# MCU.net
KiCad netlist of a schematic drawn in Altium Designer
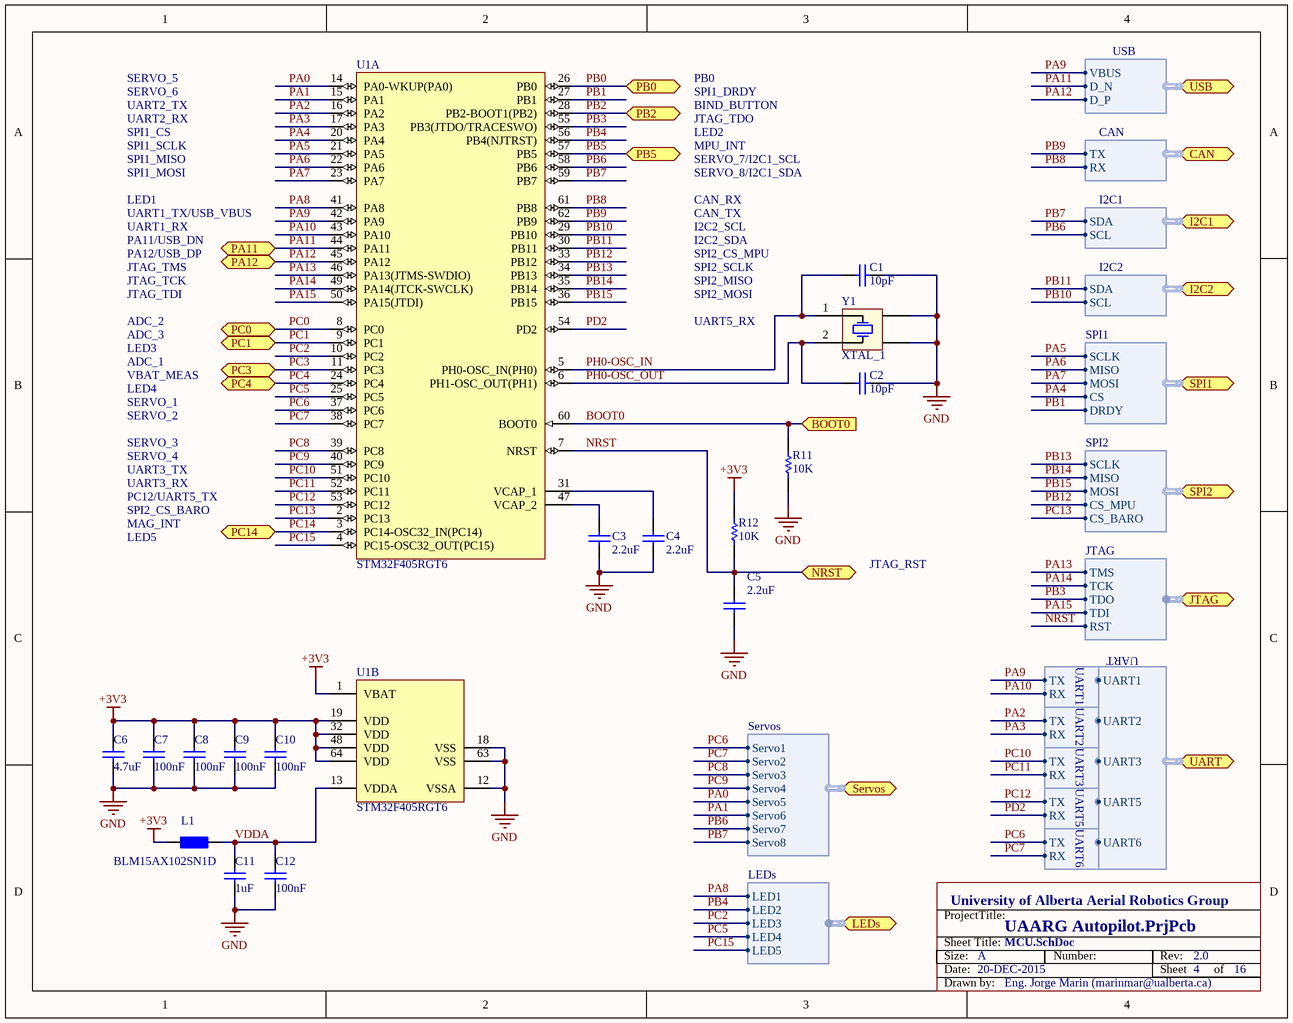
[diagram p0: MCU.SchDoc]

(export (version "E")
  (design (tool "Eeschema 10.0.6"))
  (components
    (comp (ref "C1")
      (value "10pF")
      (footprint "CAP_0402[1005M]")
      (description "Capacitor")
      (fields
        (field (name "MANUFACTURER PART NUMBER") "CC0402JRNPO9BN100")
        (field (name "MANUFACTURER") "Yageo")
      )
      (libsource (lib "UAARG Autopilot") (part "CAP"))
    )
    (comp (ref "C2")
      (value "10pF")
      (footprint "CAP_0402[1005M]")
      (description "Capacitor")
      (fields
        (field (name "MANUFACTURER PART NUMBER") "CC0402JRNPO9BN100")
        (field (name "MANUFACTURER") "Yageo")
      )
      (libsource (lib "UAARG Autopilot") (part "CAP"))
    )
    (comp (ref "C3")
      (value "2.2uF")
      (footprint "CAP_0402[1005M]")
      (description "Capacitor")
      (fields
        (field (name "MANUFACTURER") "Yageo")
        (field (name "MANUFACTURER PART NUMBER") "CC0402MRX5R5BB225")
      )
      (libsource (lib "UAARG Autopilot") (part "CAP"))
    )
    (comp (ref "C4")
      (value "2.2uF")
      (footprint "CAP_0402[1005M]")
      (description "Capacitor")
      (fields
        (field (name "MANUFACTURER") "Yageo")
        (field (name "MANUFACTURER PART NUMBER") "CC0402MRX5R5BB225")
      )
      (libsource (lib "UAARG Autopilot") (part "CAP"))
    )
    (comp (ref "C5")
      (value "2.2uF")
      (footprint "CAP_0402[1005M]")
      (description "Capacitor")
      (fields
        (field (name "MANUFACTURER") "Yageo")
        (field (name "MANUFACTURER PART NUMBER") "CC0402MRX5R5BB225")
      )
      (libsource (lib "UAARG Autopilot") (part "CAP"))
    )
    (comp (ref "C6")
      (value "4.7uF")
      (footprint "CAP_0603[1608M]")
      (description "Capacitor")
      (fields
        (field (name "MANUFACTURER") "Yageo")
        (field (name "MANUFACTURER PART NUMBER") "CC0603KRX5R6BB475")
      )
      (libsource (lib "UAARG Autopilot") (part "CAP"))
    )
    (comp (ref "C7")
      (value "100nF")
      (footprint "CAP_0402[1005M]")
      (description "CAP CER 0.1UF 10V 10% X7R 0402")
      (fields
        (field (name "MANUFACTURER") "Yageo")
        (field (name "MANUFACTURER PART NUMBER") "CC0402KRX7R6BB104")
      )
      (libsource (lib "UAARG Autopilot") (part "CAP"))
    )
    (comp (ref "C8")
      (value "100nF")
      (footprint "CAP_0402[1005M]")
      (description "CAP CER 0.1UF 10V 10% X7R 0402")
      (fields
        (field (name "MANUFACTURER") "Yageo")
        (field (name "MANUFACTURER PART NUMBER") "CC0402KRX7R6BB104")
      )
      (libsource (lib "UAARG Autopilot") (part "CAP"))
    )
    (comp (ref "C9")
      (value "100nF")
      (footprint "CAP_0402[1005M]")
      (description "CAP CER 0.1UF 10V 10% X7R 0402")
      (fields
        (field (name "MANUFACTURER") "Yageo")
        (field (name "MANUFACTURER PART NUMBER") "CC0402KRX7R6BB104")
      )
      (libsource (lib "UAARG Autopilot") (part "CAP"))
    )
    (comp (ref "C10")
      (value "100nF")
      (footprint "CAP_0402[1005M]")
      (description "CAP CER 0.1UF 10V 10% X7R 0402")
      (fields
        (field (name "MANUFACTURER") "Yageo")
        (field (name "MANUFACTURER PART NUMBER") "CC0402KRX7R6BB104")
      )
      (libsource (lib "UAARG Autopilot") (part "CAP"))
    )
    (comp (ref "C11")
      (value "1uF")
      (footprint "CAP_0402[1005M]")
      (description "Capacitor")
      (fields
        (field (name "MANUFACTURER PART NUMBER") "CC0402KRX5R5BB105")
        (field (name "MANUFACTURER") "Yageo")
      )
      (libsource (lib "UAARG Autopilot") (part "CAP"))
    )
    (comp (ref "C12")
      (value "100nF")
      (footprint "CAP_0402[1005M]")
      (description "CAP CER 0.1UF 10V 10% X7R 0402")
      (fields
        (field (name "MANUFACTURER") "Yageo")
        (field (name "MANUFACTURER PART NUMBER") "CC0402KRX7R6BB104")
      )
      (libsource (lib "UAARG Autopilot") (part "CAP"))
    )
    (comp (ref "L1")
      (value "BLM15AX102SN1D")
      (footprint "GEN_0402[1005M]")
      (description "BEAD FERRITE")
      (fields
        (field (name "MANUFACTURER") "Murata Electronics North America")
        (field (name "MANUFACTURER PART NUMBER") "BLM15AX102SN1D")
      )
      (libsource (lib "UAARG Autopilot") (part "Bead Ferrite"))
    )
    (comp (ref "R11")
      (value "10K")
      (footprint "RES_0402[1005M]")
      (description "Resistor")
      (fields
        (field (name "MANUFACTURER") "Yageo")
        (field (name "MANUFACTURER PART NUMBER") "RC0402FR-0710KL")
      )
      (libsource (lib "UAARG Autopilot") (part "RES"))
    )
    (comp (ref "R12")
      (value "10K")
      (footprint "RES_0402[1005M]")
      (description "Resistor")
      (fields
        (field (name "MANUFACTURER") "Yageo")
        (field (name "MANUFACTURER PART NUMBER") "RC0402FR-0710KL")
      )
      (libsource (lib "UAARG Autopilot") (part "RES"))
    )
    (comp (ref "U1")
      (value "STM32F405RGT6")
      (footprint "STM-LQFP64_N")
      (fields (field (name "MANUFACTURER") "STMicroelectronics"))
      (libsource (lib "UAARG Autopilot") (part "STM32F405RGT6"))
    )
    (comp (ref "Y1")
      (value "XTAL_1")
      (footprint "CRYSTAL SMD3 ABM8G 3225")
      (description "Crystal Oscillator with ground points")
      (fields
        (field (name "MANUFACTURER") "Abracon LLC")
        (field (name "MANUFACTURER PART NUMBER") "ABM8G-12.000MHZ-4Y-T3")
      )
      (libsource (lib "UAARG Autopilot") (part "XTAL_1"))
    )
  )
  (nets
    (net (code "11") (name "+3V3") (class "Default")
      (node (ref "C10") (pin "1") (pinfunction "1_1") (pintype "passive"))
      (node (ref "C6") (pin "2") (pinfunction "2_2") (pintype "passive"))
      (node (ref "C7") (pin "1") (pinfunction "1_1") (pintype "passive"))
      (node (ref "C8") (pin "1") (pinfunction "1_1") (pintype "passive"))
      (node (ref "C9") (pin "1") (pinfunction "1_1") (pintype "passive"))
      (node (ref "L1") (pin "1") (pinfunction "1_1") (pintype "passive"))
      (node (ref "R12") (pin "2") (pinfunction "2_2") (pintype "passive"))
      (node (ref "U1") (pin "1") (pinfunction "VBAT_1") (pintype "power_in"))
      (node (ref "U1") (pin "19") (pinfunction "VDD_19") (pintype "power_in"))
      (node (ref "U1") (pin "32") (pinfunction "VDD_32") (pintype "power_in"))
      (node (ref "U1") (pin "48") (pinfunction "VDD_48") (pintype "power_in"))
      (node (ref "U1") (pin "64") (pinfunction "VDD_64") (pintype "power_in"))
    )
    (net (code "12") (name "/BOOT0") (class "Default")
      (node (ref "R11") (pin "2") (pinfunction "2_2") (pintype "passive"))
      (node (ref "U1") (pin "60") (pinfunction "BOOT0_60") (pintype "input"))
    )
    (net (code "13") (name "/NRST") (class "Default")
      (node (ref "C5") (pin "2") (pinfunction "2_2") (pintype "passive"))
      (node (ref "R12") (pin "1") (pinfunction "1_1") (pintype "passive"))
      (node (ref "U1") (pin "7") (pinfunction "NRST_7") (pintype "bidirectional"))
    )
    (net (code "14") (name "/PA0") (class "Default")
      (node (ref "U1") (pin "14") (pinfunction "PA0-WKUP(PA0)_14") (pintype "bidirectional"))
    )
    (net (code "15") (name "/PA1") (class "Default")
      (node (ref "U1") (pin "15") (pinfunction "PA1_15") (pintype "bidirectional"))
    )
    (net (code "16") (name "/PA2") (class "Default")
      (node (ref "U1") (pin "16") (pinfunction "PA2_16") (pintype "bidirectional"))
    )
    (net (code "17") (name "/PA3") (class "Default")
      (node (ref "U1") (pin "17") (pinfunction "PA3_17") (pintype "bidirectional"))
    )
    (net (code "18") (name "/PA4") (class "Default")
      (node (ref "U1") (pin "20") (pinfunction "PA4_20") (pintype "bidirectional"))
    )
    (net (code "19") (name "/PA5") (class "Default")
      (node (ref "U1") (pin "21") (pinfunction "PA5_21") (pintype "bidirectional"))
    )
    (net (code "20") (name "/PA6") (class "Default")
      (node (ref "U1") (pin "22") (pinfunction "PA6_22") (pintype "bidirectional"))
    )
    (net (code "21") (name "/PA7") (class "Default")
      (node (ref "U1") (pin "23") (pinfunction "PA7_23") (pintype "bidirectional"))
    )
    (net (code "22") (name "/PA8") (class "Default")
      (node (ref "U1") (pin "41") (pinfunction "PA8_41") (pintype "bidirectional"))
    )
    (net (code "23") (name "/PA9") (class "Default")
      (node (ref "U1") (pin "42") (pinfunction "PA9_42") (pintype "bidirectional"))
    )
    (net (code "24") (name "/PA10") (class "Default")
      (node (ref "U1") (pin "43") (pinfunction "PA10_43") (pintype "bidirectional"))
    )
    (net (code "25") (name "/PA11") (class "Default")
      (node (ref "U1") (pin "44") (pinfunction "PA11_44") (pintype "bidirectional"))
    )
    (net (code "26") (name "/PA12") (class "Default")
      (node (ref "U1") (pin "45") (pinfunction "PA12_45") (pintype "bidirectional"))
    )
    (net (code "27") (name "/PA13") (class "Default")
      (node (ref "U1") (pin "46") (pinfunction "PA13(JTMS-SWDIO)_46") (pintype "bidirectional"))
    )
    (net (code "28") (name "/PA14") (class "Default")
      (node (ref "U1") (pin "49") (pinfunction "PA14(JTCK-SWCLK)_49") (pintype "bidirectional"))
    )
    (net (code "29") (name "/PA15") (class "Default")
      (node (ref "U1") (pin "50") (pinfunction "PA15(JTDI)_50") (pintype "bidirectional"))
    )
    (net (code "30") (name "/PB0") (class "Default")
      (node (ref "U1") (pin "26") (pinfunction "PB0_26") (pintype "bidirectional"))
    )
    (net (code "31") (name "/PB1") (class "Default")
      (node (ref "U1") (pin "27") (pinfunction "PB1_27") (pintype "bidirectional"))
    )
    (net (code "32") (name "/PB2") (class "Default")
      (node (ref "U1") (pin "28") (pinfunction "PB2-BOOT1(PB2)_28") (pintype "bidirectional"))
    )
    (net (code "33") (name "/PB3") (class "Default")
      (node (ref "U1") (pin "55") (pinfunction "PB3(JTDO/TRACESWO)_55") (pintype "bidirectional"))
    )
    (net (code "34") (name "/PB4") (class "Default")
      (node (ref "U1") (pin "56") (pinfunction "PB4(NJTRST)_56") (pintype "bidirectional"))
    )
    (net (code "35") (name "/PB5") (class "Default")
      (node (ref "U1") (pin "57") (pinfunction "PB5_57") (pintype "bidirectional"))
    )
    (net (code "36") (name "/PB6") (class "Default")
      (node (ref "U1") (pin "58") (pinfunction "PB6_58") (pintype "bidirectional"))
    )
    (net (code "37") (name "/PB7") (class "Default")
      (node (ref "U1") (pin "59") (pinfunction "PB7_59") (pintype "bidirectional"))
    )
    (net (code "38") (name "/PB8") (class "Default")
      (node (ref "U1") (pin "61") (pinfunction "PB8_61") (pintype "bidirectional"))
    )
    (net (code "39") (name "/PB9") (class "Default")
      (node (ref "U1") (pin "62") (pinfunction "PB9_62") (pintype "bidirectional"))
    )
    (net (code "40") (name "/PB10") (class "Default")
      (node (ref "U1") (pin "29") (pinfunction "PB10_29") (pintype "bidirectional"))
    )
    (net (code "41") (name "/PB11") (class "Default")
      (node (ref "U1") (pin "30") (pinfunction "PB11_30") (pintype "bidirectional"))
    )
    (net (code "42") (name "/PB12") (class "Default")
      (node (ref "U1") (pin "33") (pinfunction "PB12_33") (pintype "bidirectional"))
    )
    (net (code "43") (name "/PB13") (class "Default")
      (node (ref "U1") (pin "34") (pinfunction "PB13_34") (pintype "bidirectional"))
    )
    (net (code "44") (name "/PB14") (class "Default")
      (node (ref "U1") (pin "35") (pinfunction "PB14_35") (pintype "bidirectional"))
    )
    (net (code "45") (name "/PB15") (class "Default")
      (node (ref "U1") (pin "36") (pinfunction "PB15_36") (pintype "bidirectional"))
    )
    (net (code "46") (name "/PC0") (class "Default")
      (node (ref "U1") (pin "8") (pinfunction "PC0_8") (pintype "bidirectional"))
    )
    (net (code "47") (name "/PC1") (class "Default")
      (node (ref "U1") (pin "9") (pinfunction "PC1_9") (pintype "bidirectional"))
    )
    (net (code "48") (name "/PC2") (class "Default")
      (node (ref "U1") (pin "10") (pinfunction "PC2_10") (pintype "bidirectional"))
    )
    (net (code "49") (name "/PC3") (class "Default")
      (node (ref "U1") (pin "11") (pinfunction "PC3_11") (pintype "bidirectional"))
    )
    (net (code "50") (name "/PC4") (class "Default")
      (node (ref "U1") (pin "24") (pinfunction "PC4_24") (pintype "bidirectional"))
    )
    (net (code "51") (name "/PC5") (class "Default")
      (node (ref "U1") (pin "25") (pinfunction "PC5_25") (pintype "bidirectional"))
    )
    (net (code "52") (name "/PC6") (class "Default")
      (node (ref "U1") (pin "37") (pinfunction "PC6_37") (pintype "bidirectional"))
    )
    (net (code "53") (name "/PC7") (class "Default")
      (node (ref "U1") (pin "38") (pinfunction "PC7_38") (pintype "bidirectional"))
    )
    (net (code "54") (name "/PC8") (class "Default")
      (node (ref "U1") (pin "39") (pinfunction "PC8_39") (pintype "bidirectional"))
    )
    (net (code "55") (name "/PC9") (class "Default")
      (node (ref "U1") (pin "40") (pinfunction "PC9_40") (pintype "bidirectional"))
    )
    (net (code "56") (name "/PC10") (class "Default")
      (node (ref "U1") (pin "51") (pinfunction "PC10_51") (pintype "bidirectional"))
    )
    (net (code "57") (name "/PC11") (class "Default")
      (node (ref "U1") (pin "52") (pinfunction "PC11_52") (pintype "bidirectional"))
    )
    (net (code "58") (name "/PC12") (class "Default")
      (node (ref "U1") (pin "53") (pinfunction "PC12_53") (pintype "bidirectional"))
    )
    (net (code "59") (name "/PC13") (class "Default")
      (node (ref "U1") (pin "2") (pinfunction "PC13_2") (pintype "bidirectional"))
    )
    (net (code "60") (name "/PC14") (class "Default")
      (node (ref "U1") (pin "3") (pinfunction "PC14-OSC32_IN(PC14)_3") (pintype "bidirectional"))
    )
    (net (code "61") (name "/PC15") (class "Default")
      (node (ref "U1") (pin "4") (pinfunction "PC15-OSC32_OUT(PC15)_4") (pintype "bidirectional"))
    )
    (net (code "62") (name "/PD2") (class "Default")
      (node (ref "U1") (pin "54") (pinfunction "PD2_54") (pintype "bidirectional"))
    )
    (net (code "63") (name "/PH0-OSC_IN") (class "Default")
      (node (ref "C1") (pin "2") (pinfunction "2_2") (pintype "passive"))
      (node (ref "U1") (pin "5") (pinfunction "PH0-OSC_IN(PH0)_5") (pintype "bidirectional"))
      (node (ref "Y1") (pin "1") (pinfunction "OSC1_1") (pintype "passive"))
    )
    (net (code "64") (name "/PH0-OSC_OUT") (class "Default")
      (node (ref "C2") (pin "2") (pinfunction "2_2") (pintype "passive"))
      (node (ref "U1") (pin "6") (pinfunction "PH1-OSC_OUT(PH1)_6") (pintype "bidirectional"))
      (node (ref "Y1") (pin "2") (pinfunction "OSC2_2") (pintype "passive"))
    )
    (net (code "65") (name "/VDDA") (class "Default")
      (node (ref "C11") (pin "2") (pinfunction "2_2") (pintype "passive"))
      (node (ref "C12") (pin "1") (pinfunction "1_1") (pintype "passive"))
      (node (ref "L1") (pin "2") (pinfunction "2_2") (pintype "passive"))
      (node (ref "U1") (pin "13") (pinfunction "VDDA_13") (pintype "power_in"))
    )
    (net (code "76") (name "GND") (class "Default")
      (node (ref "C1") (pin "1") (pinfunction "1_1") (pintype "passive"))
      (node (ref "C10") (pin "2") (pinfunction "2_2") (pintype "passive"))
      (node (ref "C11") (pin "1") (pinfunction "1_1") (pintype "passive"))
      (node (ref "C12") (pin "2") (pinfunction "2_2") (pintype "passive"))
      (node (ref "C2") (pin "1") (pinfunction "1_1") (pintype "passive"))
      (node (ref "C3") (pin "1") (pinfunction "1_1") (pintype "passive"))
      (node (ref "C4") (pin "1") (pinfunction "1_1") (pintype "passive"))
      (node (ref "C5") (pin "1") (pinfunction "1_1") (pintype "passive"))
      (node (ref "C6") (pin "1") (pinfunction "1_1") (pintype "passive"))
      (node (ref "C7") (pin "2") (pinfunction "2_2") (pintype "passive"))
      (node (ref "C8") (pin "2") (pinfunction "2_2") (pintype "passive"))
      (node (ref "C9") (pin "2") (pinfunction "2_2") (pintype "passive"))
      (node (ref "R11") (pin "1") (pinfunction "1_1") (pintype "passive"))
      (node (ref "U1") (pin "12") (pinfunction "VSSA_12") (pintype "power_in"))
      (node (ref "U1") (pin "18") (pinfunction "VSS_18") (pintype "power_in"))
      (node (ref "U1") (pin "63") (pinfunction "VSS_63") (pintype "power_in"))
      (node (ref "Y1") (pin "3") (pinfunction "GND_3") (pintype "passive"))
      (node (ref "Y1") (pin "4") (pinfunction "GND_4") (pintype "passive"))
    )
    (net (code "77") (name "Net-(U1A-VCAP_1)") (class "Default")
      (node (ref "C4") (pin "2") (pinfunction "2_2") (pintype "passive"))
      (node (ref "U1") (pin "31") (pinfunction "VCAP_1_31") (pintype "power_in"))
    )
    (net (code "78") (name "Net-(U1A-VCAP_2)") (class "Default")
      (node (ref "C3") (pin "2") (pinfunction "2_2") (pintype "passive"))
      (node (ref "U1") (pin "47") (pinfunction "VCAP_2_47") (pintype "power_in"))
    )
  )
)
